# ECG_NEMO_final_V1B_main_stack1_fix.net
KiCad netlist of a schematic drawn in Altium Designer
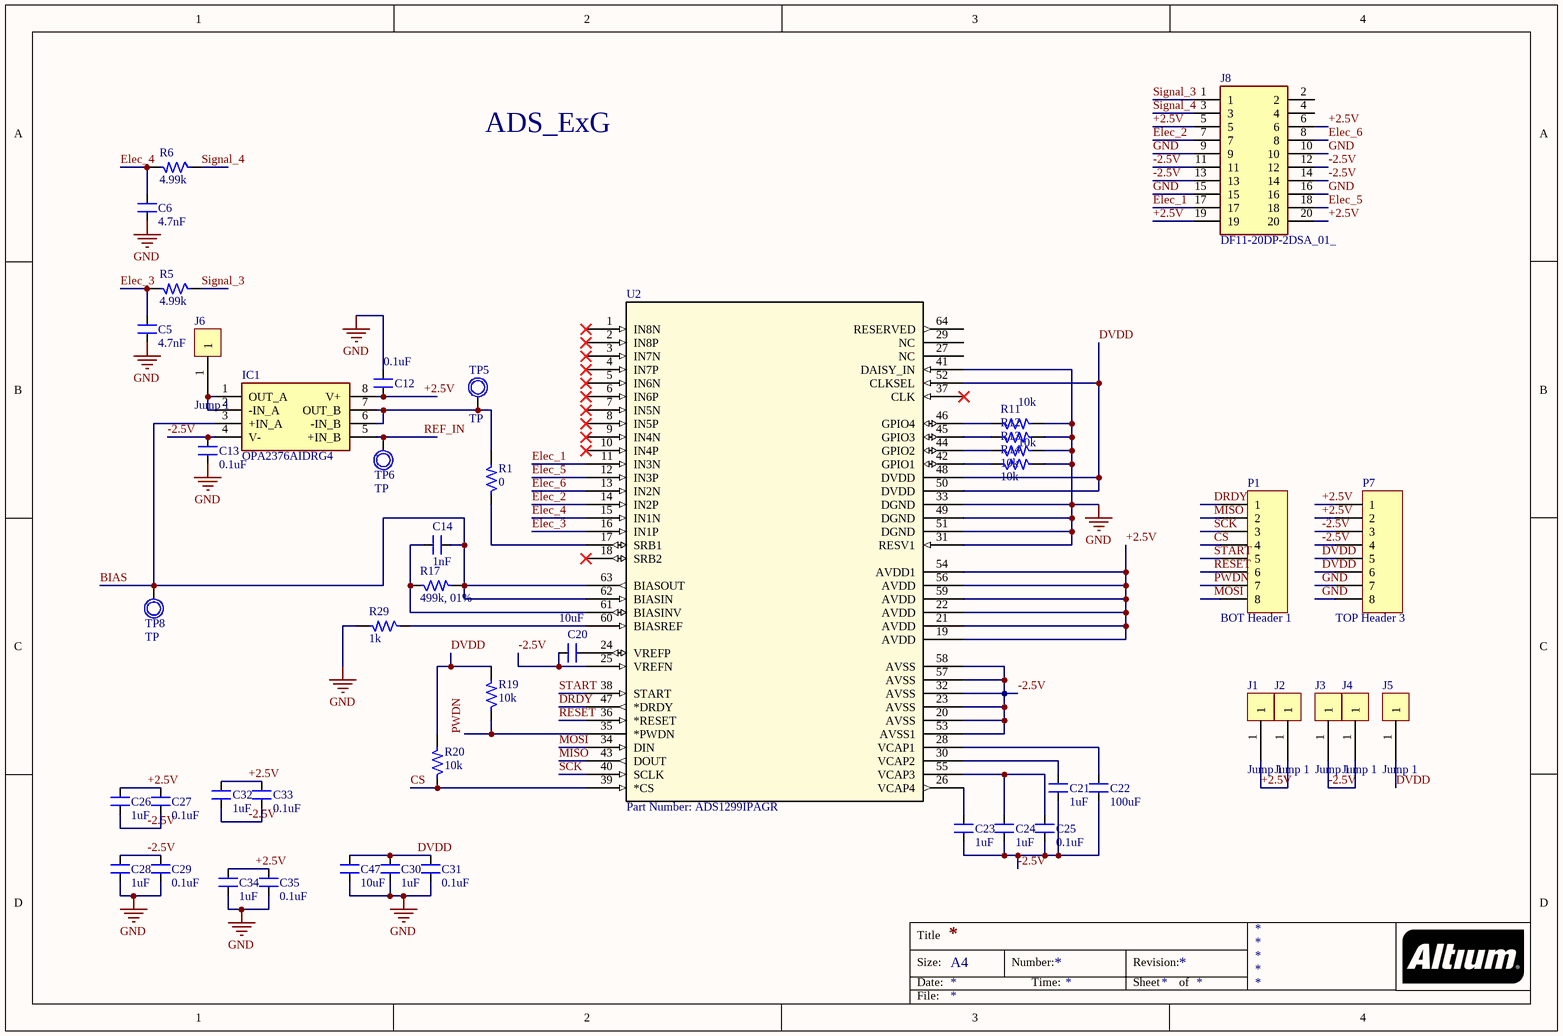
[diagram p0: ECG_NEMO_final_V1B_main_stack1_fix.schdoc]

(export (version "E")
  (design (tool "Eeschema 10.0.6"))
  (components
    (comp (ref "C5")
      (value "4.7nF")
      (footprint "SM-0805")
      (description "Cap SMD")
      (libsource (lib "VioletofSun") (part "CM"))
    )
    (comp (ref "C6")
      (value "4.7nF")
      (footprint "SM-0805")
      (description "Cap SMD")
      (libsource (lib "VioletofSun") (part "CM"))
    )
    (comp (ref "C12")
      (value "0.1uF")
      (footprint "SM-0805")
      (description "Cap SMD")
      (libsource (lib "VioletofSun") (part "CM"))
    )
    (comp (ref "C13")
      (value "0.1uF")
      (footprint "SM-0805")
      (description "Cap SMD")
      (libsource (lib "VioletofSun") (part "CM"))
    )
    (comp (ref "C14")
      (value "1nF")
      (footprint "SM-0805")
      (description "Cap SMD")
      (libsource (lib "VioletofSun") (part "CM"))
    )
    (comp (ref "C20")
      (value "10uF")
      (footprint "SM-0805")
      (description "Cap SMD")
      (libsource (lib "VioletofSun") (part "CM"))
    )
    (comp (ref "C21")
      (value "1uF")
      (footprint "SM-0805")
      (description "Cap SMD")
      (libsource (lib "VioletofSun") (part "CM"))
    )
    (comp (ref "C22")
      (value "100uF")
      (footprint "SM-0805")
      (description "Cap SMD")
      (libsource (lib "VioletofSun") (part "CM"))
    )
    (comp (ref "C23")
      (value "1uF")
      (footprint "SM-0805")
      (description "Cap SMD")
      (libsource (lib "VioletofSun") (part "CM"))
    )
    (comp (ref "C24")
      (value "1uF")
      (footprint "SM-0805")
      (description "Cap SMD")
      (libsource (lib "VioletofSun") (part "CM"))
    )
    (comp (ref "C25")
      (value "0.1uF")
      (footprint "SM-0805")
      (description "Cap SMD")
      (libsource (lib "VioletofSun") (part "CM"))
    )
    (comp (ref "C26")
      (value "1uF")
      (footprint "SM-0805")
      (description "Cap SMD")
      (libsource (lib "VioletofSun") (part "CM"))
    )
    (comp (ref "C27")
      (value "0.1uF")
      (footprint "SM-0805")
      (description "Cap SMD")
      (libsource (lib "VioletofSun") (part "CM"))
    )
    (comp (ref "C28")
      (value "1uF")
      (footprint "SM-0805")
      (description "Cap SMD")
      (libsource (lib "VioletofSun") (part "CM"))
    )
    (comp (ref "C29")
      (value "0.1uF")
      (footprint "SM-0805")
      (description "Cap SMD")
      (libsource (lib "VioletofSun") (part "CM"))
    )
    (comp (ref "C30")
      (value "1uF")
      (footprint "SM-0805")
      (description "Cap SMD")
      (libsource (lib "VioletofSun") (part "CM"))
    )
    (comp (ref "C31")
      (value "0.1uF")
      (footprint "SM-0805")
      (description "Cap SMD")
      (libsource (lib "VioletofSun") (part "CM"))
    )
    (comp (ref "C32")
      (value "1uF")
      (footprint "SM-0805")
      (description "Cap SMD")
      (libsource (lib "VioletofSun") (part "CM"))
    )
    (comp (ref "C33")
      (value "0.1uF")
      (footprint "SM-0805")
      (description "Cap SMD")
      (libsource (lib "VioletofSun") (part "CM"))
    )
    (comp (ref "C34")
      (value "1uF")
      (footprint "SM-0805")
      (description "Cap SMD")
      (libsource (lib "VioletofSun") (part "CM"))
    )
    (comp (ref "C35")
      (value "0.1uF")
      (footprint "SM-0805")
      (description "Cap SMD")
      (libsource (lib "VioletofSun") (part "CM"))
    )
    (comp (ref "C47")
      (value "10uF")
      (footprint "SM-0805")
      (description "Cap SMD")
      (libsource (lib "VioletofSun") (part "CM"))
    )
    (comp (ref "IC1")
      (value "OPA2376AIDRG4")
      (footprint "OPA2376AIDR4:SOIC127P600X175-8N")
      (description "Integrated Circuit")
      (fields (field (name "MOUSER PART NUMBER") "595-OPA2376AIDRG4"))
      (libsource (lib "OPA2376AIDR4") (part "OPA2376AIDRG4"))
    )
    (comp (ref "J1") (value "Jump 1") (footprint "PCBComponent_1") (libsource (lib "jump1") (part "jump1")))
    (comp (ref "J2") (value "Jump 1") (footprint "PCBComponent_1") (libsource (lib "jump1") (part "jump1")))
    (comp (ref "J3") (value "Jump 1") (footprint "PCBComponent_1") (libsource (lib "jump1") (part "jump1")))
    (comp (ref "J4") (value "Jump 1") (footprint "PCBComponent_1") (libsource (lib "jump1") (part "jump1")))
    (comp (ref "J5") (value "Jump 1") (footprint "PCBComponent_1") (libsource (lib "jump1") (part "jump1")))
    (comp (ref "J6") (value "Jump 1") (footprint "PCBComponent_1") (libsource (lib "jump1") (part "jump1")))
    (comp (ref "J8")
      (value "DF11-20DP-2DSA_01_")
      (footprint "20P 2.5mm")
      (description "Connector")
      (fields
        (field (name "MANUFACTURER_PART_NUMBER") "DF11-20DP-2DSA(01)")
        (field (name "MOUSER PART NUMBER") "798-DF11-20DP-2DSA01")
      )
      (libsource (lib "SamacSys") (part "DF11-20DP-2DSA_01_"))
    )
    (comp (ref "P1")
      (value "BOT Header 1")
      (footprint "HDR1X8")
      (description "Header, 8-Pin")
      (fields (field (name "PUBLISHER") "Altium Limited"))
      (libsource (lib "Miscellaneous Connectors") (part "Header 8"))
    )
    (comp (ref "P7")
      (value "TOP Header 3")
      (footprint "HDR1X8")
      (description "Header, 8-Pin")
      (fields (field (name "PUBLISHER") "Altium Limited"))
      (libsource (lib "Miscellaneous Connectors") (part "Header 8"))
    )
    (comp (ref "R1")
      (value "0")
      (footprint "SM-0805")
      (description "Resistor 1/4W")
      (libsource (lib "VioletofSun") (part "R"))
    )
    (comp (ref "R5")
      (value "4.99k")
      (footprint "SM-0805")
      (description "Resistor 1/4W")
      (libsource (lib "VioletofSun") (part "R"))
    )
    (comp (ref "R6")
      (value "4.99k")
      (footprint "SM-0805")
      (description "Resistor 1/4W")
      (libsource (lib "VioletofSun") (part "R"))
    )
    (comp (ref "R11")
      (value "10k")
      (footprint "SM-0805")
      (description "Resistor 1/4W")
      (libsource (lib "VioletofSun") (part "R"))
    )
    (comp (ref "R12")
      (value "10k")
      (footprint "SM-0805")
      (description "Resistor 1/4W")
      (libsource (lib "VioletofSun") (part "R"))
    )
    (comp (ref "R13")
      (value "10k")
      (footprint "SM-0805")
      (description "Resistor 1/4W")
      (libsource (lib "VioletofSun") (part "R"))
    )
    (comp (ref "R14")
      (value "10k")
      (footprint "SM-0805")
      (description "Resistor 1/4W")
      (libsource (lib "VioletofSun") (part "R"))
    )
    (comp (ref "R17")
      (value "499k, 01%")
      (footprint "SM-0805")
      (description "Resistor 1/4W")
      (libsource (lib "VioletofSun") (part "R"))
    )
    (comp (ref "R19")
      (value "10k")
      (footprint "SM-0805")
      (description "Resistor 1/4W")
      (libsource (lib "VioletofSun") (part "R"))
    )
    (comp (ref "R20")
      (value "10k")
      (footprint "SM-0805")
      (description "Resistor 1/4W")
      (libsource (lib "VioletofSun") (part "R"))
    )
    (comp (ref "R29")
      (value "1k")
      (footprint "SM-0805")
      (description "Resistor 1/4W")
      (libsource (lib "VioletofSun") (part "R"))
    )
    (comp (ref "TP5")
      (value "TP")
      (footprint "TP1")
      (description "Test Point")
      (libsource (lib "") (part "TP1_1"))
    )
    (comp (ref "TP6")
      (value "TP")
      (footprint "TP1")
      (description "Test Point")
      (libsource (lib "VioletofSun") (part "TP1"))
    )
    (comp (ref "TP8")
      (value "TP")
      (footprint "TP1")
      (description "Test Point")
      (libsource (lib "VioletofSun") (part "TP1"))
    )
    (comp (ref "U2")
      (value "Part Number: ADS1299IPAGR")
      (footprint "QFP50P1200X1200X120-64N")
      (description "No Description Available")
      (fields
        (field (name "MANUFACTURER_PART_NUMBER") "ADS1299IPAGR")
        (field (name "COPYRIGHT") "Copyright (C) 2018 Accelerated Designs. All rights reserved")
      )
      (libsource (lib "Flex-PCB-fmECG") (part "ADS1299IPAGR"))
    )
  )
  (nets
    (net (code "1") (name "/+2.5V") (class "Default")
      (node (ref "C12") (pin "1") (pinfunction "1_1") (pintype "passive"))
      (node (ref "C26") (pin "2") (pinfunction "2_2") (pintype "passive"))
      (node (ref "C27") (pin "2") (pinfunction "2_2") (pintype "passive"))
      (node (ref "C32") (pin "2") (pinfunction "2_2") (pintype "passive"))
      (node (ref "C33") (pin "2") (pinfunction "2_2") (pintype "passive"))
      (node (ref "C34") (pin "2") (pinfunction "2_2") (pintype "passive"))
      (node (ref "C35") (pin "2") (pinfunction "2_2") (pintype "passive"))
      (node (ref "IC1") (pin "8") (pinfunction "V+_8") (pintype "passive"))
      (node (ref "J1") (pin "1") (pinfunction "1_1") (pintype "passive"))
      (node (ref "J2") (pin "1") (pinfunction "1_1") (pintype "passive"))
      (node (ref "J8") (pin "19") (pinfunction "19_19") (pintype "passive"))
      (node (ref "J8") (pin "20") (pinfunction "20_20") (pintype "passive"))
      (node (ref "J8") (pin "5") (pinfunction "5_5") (pintype "passive"))
      (node (ref "J8") (pin "6") (pinfunction "6_6") (pintype "passive"))
      (node (ref "P7") (pin "1") (pinfunction "1_1") (pintype "passive"))
      (node (ref "P7") (pin "2") (pinfunction "2_2") (pintype "passive"))
      (node (ref "U2") (pin "19") (pinfunction "AVDD_19") (pintype "power_in"))
      (node (ref "U2") (pin "21") (pinfunction "AVDD_21") (pintype "power_in"))
      (node (ref "U2") (pin "22") (pinfunction "AVDD_22") (pintype "power_in"))
      (node (ref "U2") (pin "54") (pinfunction "AVDD1_54") (pintype "power_in"))
      (node (ref "U2") (pin "56") (pinfunction "AVDD_56") (pintype "power_in"))
      (node (ref "U2") (pin "59") (pinfunction "AVDD_59") (pintype "power_in"))
    )
    (net (code "2") (name "/-2.5V") (class "Default")
      (node (ref "C13") (pin "2") (pinfunction "2_2") (pintype "passive"))
      (node (ref "C20") (pin "2") (pinfunction "2_2") (pintype "passive"))
      (node (ref "C21") (pin "1") (pinfunction "1_1") (pintype "passive"))
      (node (ref "C22") (pin "2") (pinfunction "2_2") (pintype "passive"))
      (node (ref "C23") (pin "1") (pinfunction "1_1") (pintype "passive"))
      (node (ref "C24") (pin "1") (pinfunction "1_1") (pintype "passive"))
      (node (ref "C25") (pin "1") (pinfunction "1_1") (pintype "passive"))
      (node (ref "C26") (pin "1") (pinfunction "1_1") (pintype "passive"))
      (node (ref "C27") (pin "1") (pinfunction "1_1") (pintype "passive"))
      (node (ref "C28") (pin "2") (pinfunction "2_2") (pintype "passive"))
      (node (ref "C29") (pin "2") (pinfunction "2_2") (pintype "passive"))
      (node (ref "C32") (pin "1") (pinfunction "1_1") (pintype "passive"))
      (node (ref "C33") (pin "1") (pinfunction "1_1") (pintype "passive"))
      (node (ref "IC1") (pin "4") (pinfunction "V-_4") (pintype "passive"))
      (node (ref "J3") (pin "1") (pinfunction "1_1") (pintype "passive"))
      (node (ref "J4") (pin "1") (pinfunction "1_1") (pintype "passive"))
      (node (ref "J8") (pin "11") (pinfunction "11_11") (pintype "passive"))
      (node (ref "J8") (pin "12") (pinfunction "12_12") (pintype "passive"))
      (node (ref "J8") (pin "13") (pinfunction "13_13") (pintype "passive"))
      (node (ref "J8") (pin "14") (pinfunction "14_14") (pintype "passive"))
      (node (ref "P7") (pin "3") (pinfunction "3_3") (pintype "passive"))
      (node (ref "P7") (pin "4") (pinfunction "4_4") (pintype "passive"))
      (node (ref "U2") (pin "20") (pinfunction "AVSS_20") (pintype "power_in"))
      (node (ref "U2") (pin "23") (pinfunction "AVSS_23") (pintype "power_in"))
      (node (ref "U2") (pin "25") (pinfunction "VREFN_25") (pintype "input"))
      (node (ref "U2") (pin "32") (pinfunction "AVSS_32") (pintype "power_in"))
      (node (ref "U2") (pin "53") (pinfunction "AVSS1_53") (pintype "power_in"))
      (node (ref "U2") (pin "57") (pinfunction "AVSS_57") (pintype "power_in"))
      (node (ref "U2") (pin "58") (pinfunction "AVSS_58") (pintype "power_in"))
    )
    (net (code "3") (name "/BIAS") (class "Default")
      (node (ref "C14") (pin "2") (pinfunction "2_2") (pintype "passive"))
      (node (ref "IC1") (pin "3") (pinfunction "+IN_A_3") (pintype "passive"))
      (node (ref "R17") (pin "2") (pinfunction "2_2") (pintype "passive"))
      (node (ref "TP8") (pin "1") (pinfunction "1_1") (pintype "passive"))
      (node (ref "U2") (pin "62") (pinfunction "BIASIN_62") (pintype "input"))
      (node (ref "U2") (pin "63") (pinfunction "BIASOUT_63") (pintype "output"))
    )
    (net (code "4") (name "/CS") (class "Default")
      (node (ref "P1") (pin "4") (pinfunction "4_4") (pintype "passive"))
      (node (ref "R20") (pin "1") (pinfunction "1_1") (pintype "passive"))
      (node (ref "U2") (pin "39") (pinfunction "*CS_39") (pintype "input"))
    )
    (net (code "5") (name "/DRDY") (class "Default")
      (node (ref "P1") (pin "1") (pinfunction "1_1") (pintype "passive"))
      (node (ref "U2") (pin "47") (pinfunction "*DRDY_47") (pintype "output"))
    )
    (net (code "6") (name "/DVDD") (class "Default")
      (node (ref "C30") (pin "2") (pinfunction "2_2") (pintype "passive"))
      (node (ref "C31") (pin "2") (pinfunction "2_2") (pintype "passive"))
      (node (ref "C47") (pin "2") (pinfunction "2_2") (pintype "passive"))
      (node (ref "J5") (pin "1") (pinfunction "1_1") (pintype "passive"))
      (node (ref "P7") (pin "5") (pinfunction "5_5") (pintype "passive"))
      (node (ref "P7") (pin "6") (pinfunction "6_6") (pintype "passive"))
      (node (ref "R19") (pin "2") (pinfunction "2_2") (pintype "passive"))
      (node (ref "R20") (pin "2") (pinfunction "2_2") (pintype "passive"))
      (node (ref "U2") (pin "48") (pinfunction "DVDD_48") (pintype "power_in"))
      (node (ref "U2") (pin "50") (pinfunction "DVDD_50") (pintype "power_in"))
      (node (ref "U2") (pin "52") (pinfunction "CLKSEL_52") (pintype "input"))
    )
    (net (code "7") (name "/Elec_1") (class "Default")
      (node (ref "J8") (pin "17") (pinfunction "17_17") (pintype "passive"))
      (node (ref "U2") (pin "11") (pinfunction "IN3N_11") (pintype "input"))
    )
    (net (code "8") (name "/Elec_2") (class "Default")
      (node (ref "J8") (pin "7") (pinfunction "7_7") (pintype "passive"))
      (node (ref "U2") (pin "14") (pinfunction "IN2P_14") (pintype "input"))
    )
    (net (code "9") (name "/Elec_3") (class "Default")
      (node (ref "C5") (pin "2") (pinfunction "2_2") (pintype "passive"))
      (node (ref "R5") (pin "2") (pinfunction "2_2") (pintype "passive"))
      (node (ref "U2") (pin "16") (pinfunction "IN1P_16") (pintype "input"))
    )
    (net (code "10") (name "/Elec_4") (class "Default")
      (node (ref "C6") (pin "2") (pinfunction "2_2") (pintype "passive"))
      (node (ref "R6") (pin "2") (pinfunction "2_2") (pintype "passive"))
      (node (ref "U2") (pin "15") (pinfunction "IN1N_15") (pintype "input"))
    )
    (net (code "11") (name "/Elec_5") (class "Default")
      (node (ref "J8") (pin "18") (pinfunction "18_18") (pintype "passive"))
      (node (ref "U2") (pin "12") (pinfunction "IN3P_12") (pintype "input"))
    )
    (net (code "12") (name "/Elec_6") (class "Default")
      (node (ref "J8") (pin "8") (pinfunction "8_8") (pintype "passive"))
      (node (ref "U2") (pin "13") (pinfunction "IN2N_13") (pintype "input"))
    )
    (net (code "13") (name "/MISO") (class "Default")
      (node (ref "P1") (pin "2") (pinfunction "2_2") (pintype "passive"))
      (node (ref "U2") (pin "43") (pinfunction "DOUT_43") (pintype "output"))
    )
    (net (code "14") (name "/MOSI") (class "Default")
      (node (ref "P1") (pin "8") (pinfunction "8_8") (pintype "passive"))
      (node (ref "U2") (pin "34") (pinfunction "DIN_34") (pintype "input"))
    )
    (net (code "15") (name "/PWDN") (class "Default")
      (node (ref "P1") (pin "7") (pinfunction "7_7") (pintype "passive"))
      (node (ref "R19") (pin "1") (pinfunction "1_1") (pintype "passive"))
      (node (ref "U2") (pin "35") (pinfunction "*PWDN_35") (pintype "power_in"))
    )
    (net (code "16") (name "/REF_IN") (class "Default")
      (node (ref "IC1") (pin "5") (pinfunction "+IN_B_5") (pintype "passive"))
      (node (ref "TP6") (pin "1") (pinfunction "1_1") (pintype "passive"))
    )
    (net (code "17") (name "/RESET") (class "Default")
      (node (ref "P1") (pin "6") (pinfunction "6_6") (pintype "passive"))
      (node (ref "U2") (pin "36") (pinfunction "*RESET_36") (pintype "input"))
    )
    (net (code "18") (name "/SCK") (class "Default")
      (node (ref "P1") (pin "3") (pinfunction "3_3") (pintype "passive"))
      (node (ref "U2") (pin "40") (pinfunction "SCLK_40") (pintype "input"))
    )
    (net (code "19") (name "/START") (class "Default")
      (node (ref "P1") (pin "5") (pinfunction "5_5") (pintype "passive"))
      (node (ref "U2") (pin "38") (pinfunction "START_38") (pintype "input"))
    )
    (net (code "20") (name "/Signal_3") (class "Default")
      (node (ref "J8") (pin "1") (pinfunction "1_1") (pintype "passive"))
      (node (ref "R5") (pin "1") (pinfunction "1_1") (pintype "passive"))
    )
    (net (code "21") (name "/Signal_4") (class "Default")
      (node (ref "J8") (pin "3") (pinfunction "3_3") (pintype "passive"))
      (node (ref "R6") (pin "1") (pinfunction "1_1") (pintype "passive"))
    )
    (net (code "22") (name "GND") (class "Default")
      (node (ref "C12") (pin "2") (pinfunction "2_2") (pintype "passive"))
      (node (ref "C13") (pin "1") (pinfunction "1_1") (pintype "passive"))
      (node (ref "C28") (pin "1") (pinfunction "1_1") (pintype "passive"))
      (node (ref "C29") (pin "1") (pinfunction "1_1") (pintype "passive"))
      (node (ref "C30") (pin "1") (pinfunction "1_1") (pintype "passive"))
      (node (ref "C31") (pin "1") (pinfunction "1_1") (pintype "passive"))
      (node (ref "C34") (pin "1") (pinfunction "1_1") (pintype "passive"))
      (node (ref "C35") (pin "1") (pinfunction "1_1") (pintype "passive"))
      (node (ref "C47") (pin "1") (pinfunction "1_1") (pintype "passive"))
      (node (ref "C5") (pin "1") (pinfunction "1_1") (pintype "passive"))
      (node (ref "C6") (pin "1") (pinfunction "1_1") (pintype "passive"))
      (node (ref "J8") (pin "10") (pinfunction "10_10") (pintype "passive"))
      (node (ref "J8") (pin "15") (pinfunction "15_15") (pintype "passive"))
      (node (ref "J8") (pin "16") (pinfunction "16_16") (pintype "passive"))
      (node (ref "J8") (pin "9") (pinfunction "9_9") (pintype "passive"))
      (node (ref "P7") (pin "7") (pinfunction "7_7") (pintype "passive"))
      (node (ref "P7") (pin "8") (pinfunction "8_8") (pintype "passive"))
      (node (ref "R11") (pin "2") (pinfunction "2_2") (pintype "passive"))
      (node (ref "R12") (pin "2") (pinfunction "2_2") (pintype "passive"))
      (node (ref "R13") (pin "2") (pinfunction "2_2") (pintype "passive"))
      (node (ref "R14") (pin "2") (pinfunction "2_2") (pintype "passive"))
      (node (ref "R29") (pin "2") (pinfunction "2_2") (pintype "passive"))
      (node (ref "U2") (pin "31") (pinfunction "RESV1_31") (pintype "input"))
      (node (ref "U2") (pin "33") (pinfunction "DGND_33") (pintype "power_in"))
      (node (ref "U2") (pin "41") (pinfunction "DAISY_IN_41") (pintype "input"))
      (node (ref "U2") (pin "49") (pinfunction "DGND_49") (pintype "power_in"))
      (node (ref "U2") (pin "51") (pinfunction "DGND_51") (pintype "power_in"))
    )
    (net (code "23") (name "Net-(IC1--IN_A)") (class "Default")
      (node (ref "IC1") (pin "1") (pinfunction "OUT_A_1") (pintype "passive"))
      (node (ref "IC1") (pin "2") (pinfunction "-IN_A_2") (pintype "passive"))
      (node (ref "J6") (pin "1") (pinfunction "1_1") (pintype "passive"))
    )
    (net (code "24") (name "Net-(IC1--IN_B)") (class "Default")
      (node (ref "IC1") (pin "6") (pinfunction "-IN_B_6") (pintype "passive"))
      (node (ref "IC1") (pin "7") (pinfunction "OUT_B_7") (pintype "passive"))
      (node (ref "R1") (pin "2") (pinfunction "2_2") (pintype "passive"))
      (node (ref "TP5") (pin "1") (pinfunction "1_1") (pintype "passive"))
    )
    (net (code "25") (name "Net-(U2-BIASINV)") (class "Default")
      (node (ref "C14") (pin "1") (pinfunction "1_1") (pintype "passive"))
      (node (ref "R17") (pin "1") (pinfunction "1_1") (pintype "passive"))
      (node (ref "U2") (pin "61") (pinfunction "BIASINV_61") (pintype "bidirectional"))
    )
    (net (code "26") (name "Net-(U2-BIASREF)") (class "Default")
      (node (ref "R29") (pin "1") (pinfunction "1_1") (pintype "passive"))
      (node (ref "U2") (pin "60") (pinfunction "BIASREF_60") (pintype "input"))
    )
    (net (code "27") (name "Net-(U2-GPIO1)") (class "Default")
      (node (ref "R14") (pin "1") (pinfunction "1_1") (pintype "passive"))
      (node (ref "U2") (pin "42") (pinfunction "GPIO1_42") (pintype "bidirectional"))
    )
    (net (code "28") (name "Net-(U2-GPIO2)") (class "Default")
      (node (ref "R13") (pin "1") (pinfunction "1_1") (pintype "passive"))
      (node (ref "U2") (pin "44") (pinfunction "GPIO2_44") (pintype "bidirectional"))
    )
    (net (code "29") (name "Net-(U2-GPIO3)") (class "Default")
      (node (ref "R12") (pin "1") (pinfunction "1_1") (pintype "passive"))
      (node (ref "U2") (pin "45") (pinfunction "GPIO3_45") (pintype "bidirectional"))
    )
    (net (code "30") (name "Net-(U2-GPIO4)") (class "Default")
      (node (ref "R11") (pin "1") (pinfunction "1_1") (pintype "passive"))
      (node (ref "U2") (pin "46") (pinfunction "GPIO4_46") (pintype "bidirectional"))
    )
    (net (code "31") (name "Net-(U2-SRB1)") (class "Default")
      (node (ref "R1") (pin "1") (pinfunction "1_1") (pintype "passive"))
      (node (ref "U2") (pin "17") (pinfunction "SRB1_17") (pintype "bidirectional"))
    )
    (net (code "32") (name "Net-(U2-VCAP1)") (class "Default")
      (node (ref "C22") (pin "1") (pinfunction "1_1") (pintype "passive"))
      (node (ref "U2") (pin "28") (pinfunction "VCAP1_28") (pintype "passive"))
    )
    (net (code "33") (name "Net-(U2-VCAP2)") (class "Default")
      (node (ref "C21") (pin "2") (pinfunction "2_2") (pintype "passive"))
      (node (ref "U2") (pin "30") (pinfunction "VCAP2_30") (pintype "passive"))
    )
    (net (code "34") (name "Net-(U2-VCAP3)") (class "Default")
      (node (ref "C24") (pin "2") (pinfunction "2_2") (pintype "passive"))
      (node (ref "C25") (pin "2") (pinfunction "2_2") (pintype "passive"))
      (node (ref "U2") (pin "55") (pinfunction "VCAP3_55") (pintype "passive"))
    )
    (net (code "35") (name "Net-(U2-VCAP4)") (class "Default")
      (node (ref "C23") (pin "2") (pinfunction "2_2") (pintype "passive"))
      (node (ref "U2") (pin "26") (pinfunction "VCAP4_26") (pintype "output"))
    )
    (net (code "36") (name "Net-(U2-VREFP)") (class "Default")
      (node (ref "C20") (pin "1") (pinfunction "1_1") (pintype "passive"))
      (node (ref "U2") (pin "24") (pinfunction "VREFP_24") (pintype "bidirectional"))
    )
    (net (code "37") (name "unconnected-(J8-Pad2)") (class "Default")
      (node (ref "J8") (pin "2") (pinfunction "2_2") (pintype "passive"))
    )
    (net (code "38") (name "unconnected-(J8-Pad4)") (class "Default")
      (node (ref "J8") (pin "4") (pinfunction "4_4") (pintype "passive"))
    )
    (net (code "39") (name "unconnected-(U2-CLK-Pad37)") (class "Default")
      (node (ref "U2") (pin "37") (pinfunction "CLK_37") (pintype "input+no_connect"))
    )
    (net (code "40") (name "unconnected-(U2-IN4N-Pad9)") (class "Default")
      (node (ref "U2") (pin "9") (pinfunction "IN4N_9") (pintype "input+no_connect"))
    )
    (net (code "41") (name "unconnected-(U2-IN4P-Pad10)") (class "Default")
      (node (ref "U2") (pin "10") (pinfunction "IN4P_10") (pintype "input+no_connect"))
    )
    (net (code "42") (name "unconnected-(U2-IN5N-Pad7)") (class "Default")
      (node (ref "U2") (pin "7") (pinfunction "IN5N_7") (pintype "input+no_connect"))
    )
    (net (code "43") (name "unconnected-(U2-IN5P-Pad8)") (class "Default")
      (node (ref "U2") (pin "8") (pinfunction "IN5P_8") (pintype "input+no_connect"))
    )
    (net (code "44") (name "unconnected-(U2-IN6N-Pad5)") (class "Default")
      (node (ref "U2") (pin "5") (pinfunction "IN6N_5") (pintype "input+no_connect"))
    )
    (net (code "45") (name "unconnected-(U2-IN6P-Pad6)") (class "Default")
      (node (ref "U2") (pin "6") (pinfunction "IN6P_6") (pintype "input+no_connect"))
    )
    (net (code "46") (name "unconnected-(U2-IN7N-Pad3)") (class "Default")
      (node (ref "U2") (pin "3") (pinfunction "IN7N_3") (pintype "input+no_connect"))
    )
    (net (code "47") (name "unconnected-(U2-IN7P-Pad4)") (class "Default")
      (node (ref "U2") (pin "4") (pinfunction "IN7P_4") (pintype "input+no_connect"))
    )
    (net (code "48") (name "unconnected-(U2-IN8N-Pad1)") (class "Default")
      (node (ref "U2") (pin "1") (pinfunction "IN8N_1") (pintype "input+no_connect"))
    )
    (net (code "49") (name "unconnected-(U2-IN8P-Pad2)") (class "Default")
      (node (ref "U2") (pin "2") (pinfunction "IN8P_2") (pintype "input+no_connect"))
    )
    (net (code "50") (name "unconnected-(U2-NC-Pad27)") (class "Default")
      (node (ref "U2") (pin "27") (pinfunction "NC_27") (pintype "passive"))
    )
    (net (code "51") (name "unconnected-(U2-NC-Pad29)") (class "Default")
      (node (ref "U2") (pin "29") (pinfunction "NC_29") (pintype "passive"))
    )
    (net (code "52") (name "unconnected-(U2-RESERVED-Pad64)") (class "Default")
      (node (ref "U2") (pin "64") (pinfunction "RESERVED_64") (pintype "output"))
    )
    (net (code "53") (name "unconnected-(U2-SRB2-Pad18)") (class "Default")
      (node (ref "U2") (pin "18") (pinfunction "SRB2_18") (pintype "bidirectional+no_connect"))
    )
  )
)
